# SRAM_R1LV1616RSA.net
KiCad netlist of a schematic drawn in Altium Designer
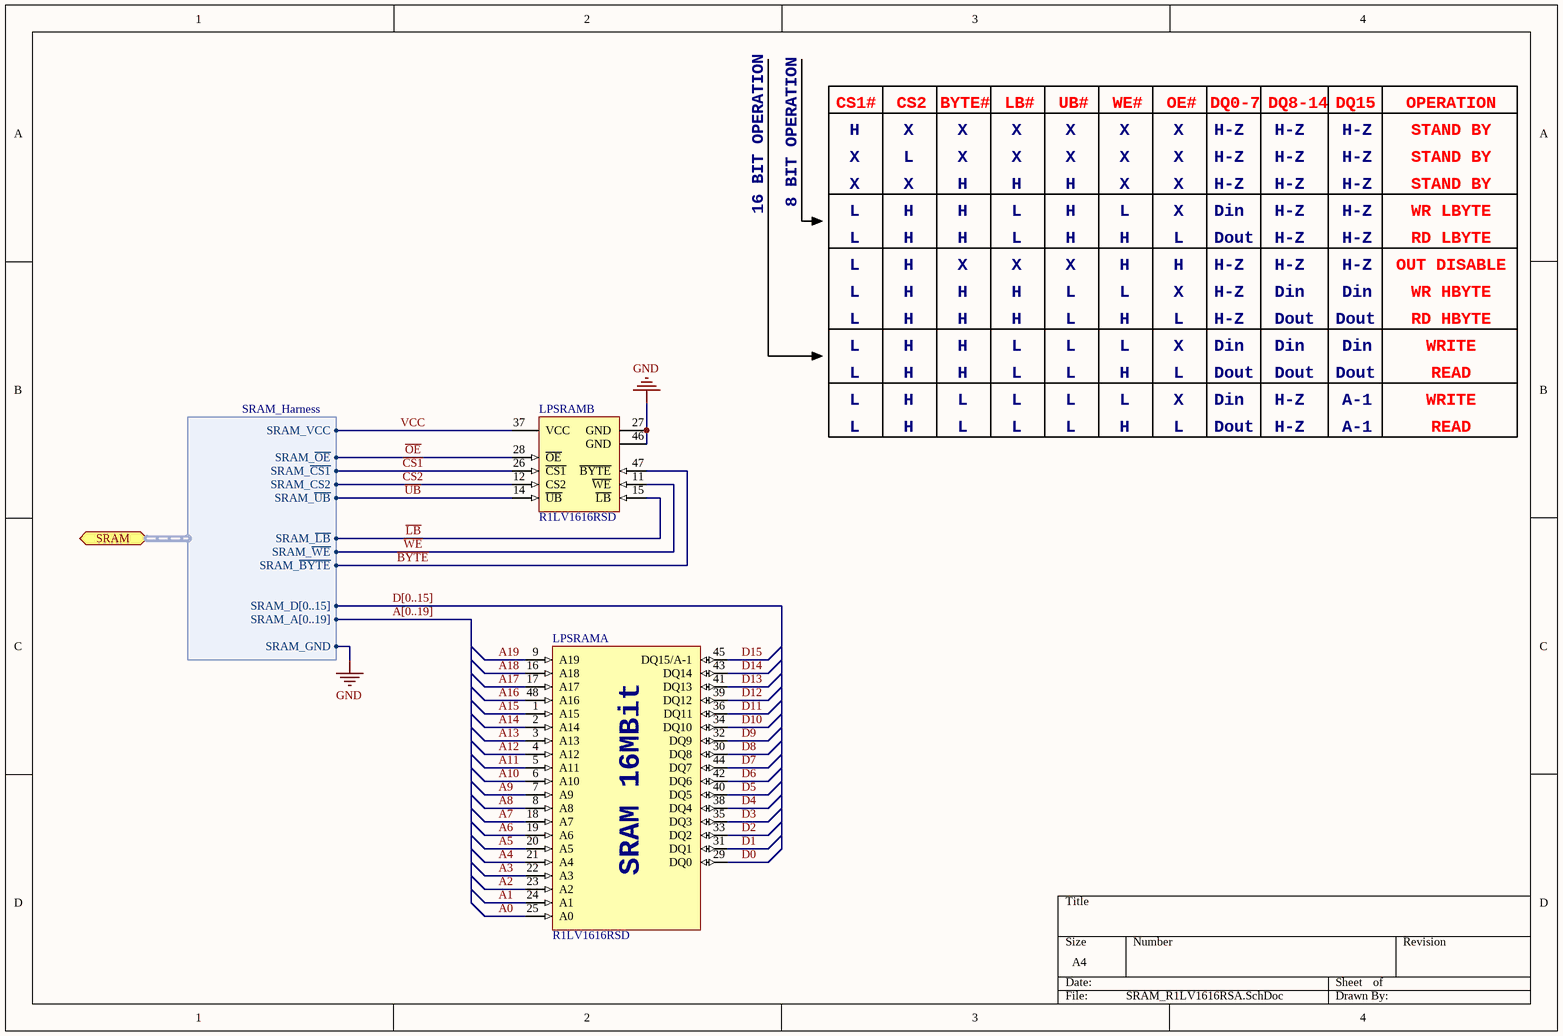
[diagram p0: SRAM_R1LV1616RSA.SchDoc]

(export (version "E")
  (design (tool "Eeschema 10.0.6"))
  (components
    (comp (ref "LPSRAM")
      (value "R1LV1616RSD")
      (footprint "TSOP48")
      (description "16Mb Advanced LPSRAM")
      (fields (field (name "DIGI-KEY PART NUMBER") "R1LV1616RSA-5SI#B0-ND"))
      (libsource (lib "IntegrationCircuits") (part "R1LV1616RSD"))
    )
  )
  (nets
    (net (code "2") (name "/A0") (class "Default")
      (node (ref "LPSRAM") (pin "25") (pinfunction "A0_25") (pintype "input"))
    )
    (net (code "3") (name "/A1") (class "Default")
      (node (ref "LPSRAM") (pin "24") (pinfunction "A1_24") (pintype "input"))
    )
    (net (code "4") (name "/A2") (class "Default")
      (node (ref "LPSRAM") (pin "23") (pinfunction "A2_23") (pintype "input"))
    )
    (net (code "5") (name "/A3") (class "Default")
      (node (ref "LPSRAM") (pin "22") (pinfunction "A3_22") (pintype "input"))
    )
    (net (code "6") (name "/A4") (class "Default")
      (node (ref "LPSRAM") (pin "21") (pinfunction "A4_21") (pintype "input"))
    )
    (net (code "7") (name "/A5") (class "Default")
      (node (ref "LPSRAM") (pin "20") (pinfunction "A5_20") (pintype "input"))
    )
    (net (code "8") (name "/A6") (class "Default")
      (node (ref "LPSRAM") (pin "19") (pinfunction "A6_19") (pintype "input"))
    )
    (net (code "9") (name "/A7") (class "Default")
      (node (ref "LPSRAM") (pin "18") (pinfunction "A7_18") (pintype "input"))
    )
    (net (code "10") (name "/A8") (class "Default")
      (node (ref "LPSRAM") (pin "8") (pinfunction "A8_8") (pintype "input"))
    )
    (net (code "11") (name "/A9") (class "Default")
      (node (ref "LPSRAM") (pin "7") (pinfunction "A9_7") (pintype "input"))
    )
    (net (code "12") (name "/A10") (class "Default")
      (node (ref "LPSRAM") (pin "6") (pinfunction "A10_6") (pintype "input"))
    )
    (net (code "13") (name "/A11") (class "Default")
      (node (ref "LPSRAM") (pin "5") (pinfunction "A11_5") (pintype "input"))
    )
    (net (code "14") (name "/A12") (class "Default")
      (node (ref "LPSRAM") (pin "4") (pinfunction "A12_4") (pintype "input"))
    )
    (net (code "15") (name "/A13") (class "Default")
      (node (ref "LPSRAM") (pin "3") (pinfunction "A13_3") (pintype "input"))
    )
    (net (code "16") (name "/A14") (class "Default")
      (node (ref "LPSRAM") (pin "2") (pinfunction "A14_2") (pintype "input"))
    )
    (net (code "17") (name "/A15") (class "Default")
      (node (ref "LPSRAM") (pin "1") (pinfunction "A15_1") (pintype "input"))
    )
    (net (code "18") (name "/A16") (class "Default")
      (node (ref "LPSRAM") (pin "48") (pinfunction "A16_48") (pintype "input"))
    )
    (net (code "19") (name "/A17") (class "Default")
      (node (ref "LPSRAM") (pin "17") (pinfunction "A17_17") (pintype "input"))
    )
    (net (code "20") (name "/A18") (class "Default")
      (node (ref "LPSRAM") (pin "16") (pinfunction "A18_16") (pintype "input"))
    )
    (net (code "21") (name "/A19") (class "Default")
      (node (ref "LPSRAM") (pin "9") (pinfunction "A19_9") (pintype "input"))
    )
    (net (code "23") (name "/CS2") (class "Default")
      (node (ref "LPSRAM") (pin "12") (pinfunction "CS2_12") (pintype "input"))
    )
    (net (code "24") (name "/D0") (class "Default")
      (node (ref "LPSRAM") (pin "29") (pinfunction "DQ0_29") (pintype "bidirectional"))
    )
    (net (code "25") (name "/D1") (class "Default")
      (node (ref "LPSRAM") (pin "31") (pinfunction "DQ1_31") (pintype "bidirectional"))
    )
    (net (code "26") (name "/D2") (class "Default")
      (node (ref "LPSRAM") (pin "33") (pinfunction "DQ2_33") (pintype "bidirectional"))
    )
    (net (code "27") (name "/D3") (class "Default")
      (node (ref "LPSRAM") (pin "35") (pinfunction "DQ3_35") (pintype "bidirectional"))
    )
    (net (code "28") (name "/D4") (class "Default")
      (node (ref "LPSRAM") (pin "38") (pinfunction "DQ4_38") (pintype "bidirectional"))
    )
    (net (code "29") (name "/D5") (class "Default")
      (node (ref "LPSRAM") (pin "40") (pinfunction "DQ5_40") (pintype "bidirectional"))
    )
    (net (code "30") (name "/D6") (class "Default")
      (node (ref "LPSRAM") (pin "42") (pinfunction "DQ6_42") (pintype "bidirectional"))
    )
    (net (code "31") (name "/D7") (class "Default")
      (node (ref "LPSRAM") (pin "44") (pinfunction "DQ7_44") (pintype "bidirectional"))
    )
    (net (code "32") (name "/D8") (class "Default")
      (node (ref "LPSRAM") (pin "30") (pinfunction "DQ8_30") (pintype "bidirectional"))
    )
    (net (code "33") (name "/D9") (class "Default")
      (node (ref "LPSRAM") (pin "32") (pinfunction "DQ9_32") (pintype "bidirectional"))
    )
    (net (code "34") (name "/D10") (class "Default")
      (node (ref "LPSRAM") (pin "34") (pinfunction "DQ10_34") (pintype "bidirectional"))
    )
    (net (code "35") (name "/D11") (class "Default")
      (node (ref "LPSRAM") (pin "36") (pinfunction "DQ11_36") (pintype "bidirectional"))
    )
    (net (code "36") (name "/D12") (class "Default")
      (node (ref "LPSRAM") (pin "39") (pinfunction "DQ12_39") (pintype "bidirectional"))
    )
    (net (code "37") (name "/D13") (class "Default")
      (node (ref "LPSRAM") (pin "41") (pinfunction "DQ13_41") (pintype "bidirectional"))
    )
    (net (code "38") (name "/D14") (class "Default")
      (node (ref "LPSRAM") (pin "43") (pinfunction "DQ14_43") (pintype "bidirectional"))
    )
    (net (code "39") (name "/D15") (class "Default")
      (node (ref "LPSRAM") (pin "45") (pinfunction "DQ15/A-1_45") (pintype "bidirectional"))
    )
    (net (code "41") (name "/VCC") (class "Default")
      (node (ref "LPSRAM") (pin "37") (pinfunction "VCC_37") (pintype "power_in"))
    )
    (net (code "43") (name "/~{BYTE}") (class "Default")
      (node (ref "LPSRAM") (pin "47") (pinfunction "~{BYTE}_47") (pintype "input"))
    )
    (net (code "44") (name "/~{CS1}") (class "Default")
      (node (ref "LPSRAM") (pin "26") (pinfunction "~{CS1}_26") (pintype "input"))
    )
    (net (code "45") (name "/~{LB}") (class "Default")
      (node (ref "LPSRAM") (pin "15") (pinfunction "~{LB}_15") (pintype "input"))
    )
    (net (code "46") (name "/~{OE}") (class "Default")
      (node (ref "LPSRAM") (pin "28") (pinfunction "~{OE}_28") (pintype "input"))
    )
    (net (code "47") (name "/~{UB}") (class "Default")
      (node (ref "LPSRAM") (pin "14") (pinfunction "~{UB}_14") (pintype "input"))
    )
    (net (code "48") (name "/~{WE}") (class "Default")
      (node (ref "LPSRAM") (pin "11") (pinfunction "~{WE}_11") (pintype "input"))
    )
    (net (code "49") (name "GND") (class "Default")
      (node (ref "LPSRAM") (pin "27") (pinfunction "GND_27") (pintype "power_in"))
      (node (ref "LPSRAM") (pin "46") (pinfunction "GND_46") (pintype "power_in"))
    )
  )
)
